# QCopterRC_LCD_Sch.net
KiCad netlist of a schematic drawn in Altium Designer
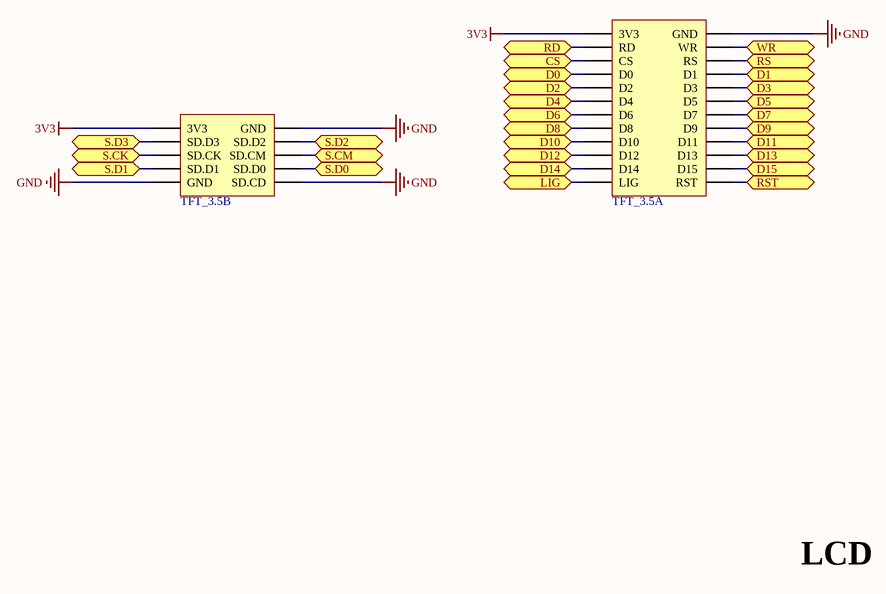
[diagram p0: QCopterRC_LCD_Sch.SchDoc]

(export (version "E")
  (design (tool "Eeschema 10.0.6"))
  (components
    (comp (ref "TFT_3.5")
      (value "TFT_3.5")
      (footprint "PCB_Module:TFT_3.5_480*320")
      (description "Module")
      (libsource (lib "SCH_Module") (part "TFT_3.5_480*320"))
    )
  )
  (nets
    (net (code "1") (name "/CS") (class "Default")
      (node (ref "TFT_3.5") (pin "5") (pinfunction "CS_5") (pintype "passive"))
    )
    (net (code "2") (name "/D0") (class "Default")
      (node (ref "TFT_3.5") (pin "7") (pinfunction "D0_7") (pintype "passive"))
    )
    (net (code "3") (name "/D1") (class "Default")
      (node (ref "TFT_3.5") (pin "8") (pinfunction "D1_8") (pintype "passive"))
    )
    (net (code "4") (name "/D2") (class "Default")
      (node (ref "TFT_3.5") (pin "9") (pinfunction "D2_9") (pintype "passive"))
    )
    (net (code "5") (name "/D3") (class "Default")
      (node (ref "TFT_3.5") (pin "10") (pinfunction "D3_10") (pintype "passive"))
    )
    (net (code "6") (name "/D4") (class "Default")
      (node (ref "TFT_3.5") (pin "11") (pinfunction "D4_11") (pintype "passive"))
    )
    (net (code "7") (name "/D5") (class "Default")
      (node (ref "TFT_3.5") (pin "12") (pinfunction "D5_12") (pintype "passive"))
    )
    (net (code "8") (name "/D6") (class "Default")
      (node (ref "TFT_3.5") (pin "13") (pinfunction "D6_13") (pintype "passive"))
    )
    (net (code "9") (name "/D7") (class "Default")
      (node (ref "TFT_3.5") (pin "14") (pinfunction "D7_14") (pintype "passive"))
    )
    (net (code "10") (name "/D8") (class "Default")
      (node (ref "TFT_3.5") (pin "15") (pinfunction "D8_15") (pintype "passive"))
    )
    (net (code "11") (name "/D9") (class "Default")
      (node (ref "TFT_3.5") (pin "16") (pinfunction "D9_16") (pintype "passive"))
    )
    (net (code "12") (name "/D10") (class "Default")
      (node (ref "TFT_3.5") (pin "17") (pinfunction "D10_17") (pintype "passive"))
    )
    (net (code "13") (name "/D11") (class "Default")
      (node (ref "TFT_3.5") (pin "18") (pinfunction "D11_18") (pintype "passive"))
    )
    (net (code "14") (name "/D12") (class "Default")
      (node (ref "TFT_3.5") (pin "19") (pinfunction "D12_19") (pintype "passive"))
    )
    (net (code "15") (name "/D13") (class "Default")
      (node (ref "TFT_3.5") (pin "20") (pinfunction "D13_20") (pintype "passive"))
    )
    (net (code "16") (name "/D14") (class "Default")
      (node (ref "TFT_3.5") (pin "21") (pinfunction "D14_21") (pintype "passive"))
    )
    (net (code "17") (name "/D15") (class "Default")
      (node (ref "TFT_3.5") (pin "22") (pinfunction "D15_22") (pintype "passive"))
    )
    (net (code "18") (name "/LIG") (class "Default")
      (node (ref "TFT_3.5") (pin "23") (pinfunction "LIG_23") (pintype "passive"))
    )
    (net (code "19") (name "/RD") (class "Default")
      (node (ref "TFT_3.5") (pin "3") (pinfunction "RD_3") (pintype "passive"))
    )
    (net (code "20") (name "/RS") (class "Default")
      (node (ref "TFT_3.5") (pin "6") (pinfunction "RS_6") (pintype "passive"))
    )
    (net (code "21") (name "/RST") (class "Default")
      (node (ref "TFT_3.5") (pin "24") (pinfunction "RST_24") (pintype "passive"))
    )
    (net (code "22") (name "/S.CK") (class "Default")
      (node (ref "TFT_3.5") (pin "29") (pinfunction "SD.CK_29") (pintype "passive"))
    )
    (net (code "23") (name "/S.CM") (class "Default")
      (node (ref "TFT_3.5") (pin "30") (pinfunction "SD.CM_30") (pintype "passive"))
    )
    (net (code "24") (name "/S.D0") (class "Default")
      (node (ref "TFT_3.5") (pin "32") (pinfunction "SD.D0_32") (pintype "passive"))
    )
    (net (code "25") (name "/S.D1") (class "Default")
      (node (ref "TFT_3.5") (pin "31") (pinfunction "SD.D1_31") (pintype "passive"))
    )
    (net (code "26") (name "/S.D2") (class "Default")
      (node (ref "TFT_3.5") (pin "28") (pinfunction "SD.D2_28") (pintype "passive"))
    )
    (net (code "27") (name "/S.D3") (class "Default")
      (node (ref "TFT_3.5") (pin "27") (pinfunction "SD.D3_27") (pintype "passive"))
    )
    (net (code "28") (name "/WR") (class "Default")
      (node (ref "TFT_3.5") (pin "4") (pinfunction "WR_4") (pintype "passive"))
    )
    (net (code "29") (name "3V3") (class "Default")
      (node (ref "TFT_3.5") (pin "1") (pinfunction "3V3_1") (pintype "passive"))
      (node (ref "TFT_3.5") (pin "25") (pinfunction "3V3_25") (pintype "passive"))
    )
    (net (code "30") (name "GND") (class "Default")
      (node (ref "TFT_3.5") (pin "2") (pinfunction "GND_2") (pintype "passive"))
      (node (ref "TFT_3.5") (pin "26") (pinfunction "GND_26") (pintype "passive"))
      (node (ref "TFT_3.5") (pin "33") (pinfunction "GND_33") (pintype "passive"))
      (node (ref "TFT_3.5") (pin "34") (pinfunction "SD.CD_34") (pintype "passive"))
    )
  )
)
